# SCH-10-Power_Connectors_copy.net
KiCad netlist of a schematic drawn in Altium Designer
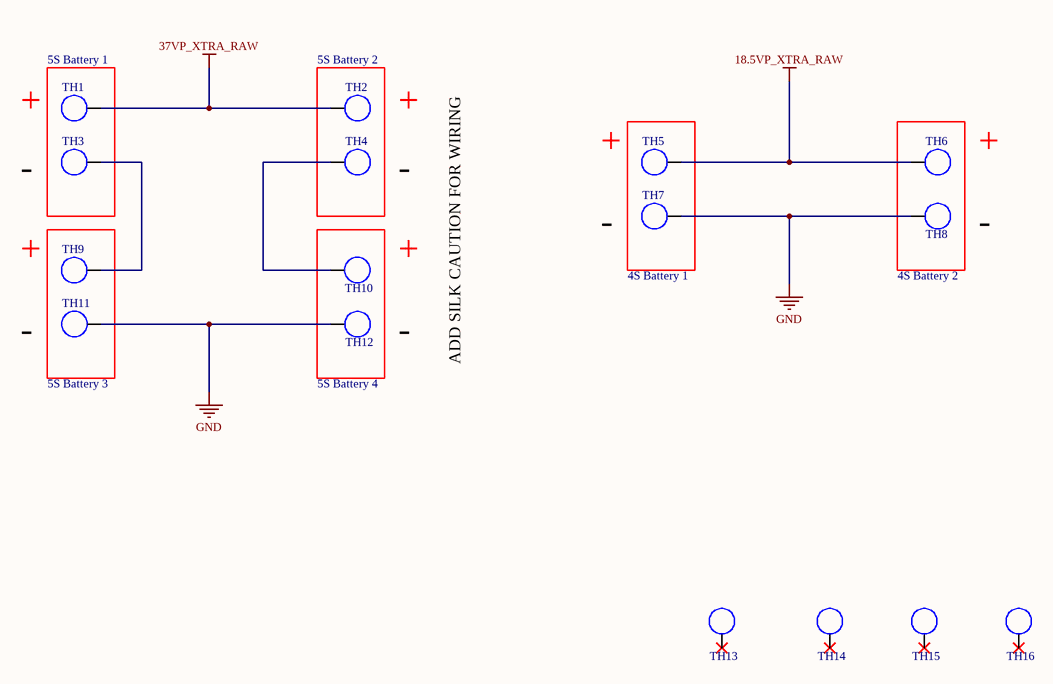
[diagram p0: SCH-10-Power Connectors_copy.SchDoc]

(export (version "E")
  (design (tool "Eeschema 10.0.6"))
  (components
    (comp (ref "TH1")
      (value "12AWG_TH")
      (footprint "m3screw")
      (libsource (lib "RSX_Mechanicals") (part "12AWG_TH"))
    )
    (comp (ref "TH2")
      (value "12AWG_TH")
      (footprint "m3screw")
      (libsource (lib "RSX_Mechanicals") (part "12AWG_TH"))
    )
    (comp (ref "TH3")
      (value "12AWG_TH")
      (footprint "m3screw")
      (libsource (lib "RSX_Mechanicals") (part "12AWG_TH"))
    )
    (comp (ref "TH4")
      (value "12AWG_TH")
      (footprint "m3screw")
      (libsource (lib "RSX_Mechanicals") (part "12AWG_TH"))
    )
    (comp (ref "TH5")
      (value "10AWG_TH")
      (footprint "m3screw")
      (libsource (lib "RSX_Mechanicals") (part "10AWG_TH"))
    )
    (comp (ref "TH6")
      (value "10AWG_TH")
      (footprint "m3screw")
      (libsource (lib "RSX_Mechanicals") (part "10AWG_TH"))
    )
    (comp (ref "TH7")
      (value "10AWG_TH")
      (footprint "m3screw")
      (libsource (lib "RSX_Mechanicals") (part "10AWG_TH"))
    )
    (comp (ref "TH8")
      (value "10AWG_TH")
      (footprint "m3screw")
      (libsource (lib "RSX_Mechanicals") (part "10AWG_TH"))
    )
    (comp (ref "TH9")
      (value "10AWG_TH")
      (footprint "m3screw")
      (libsource (lib "RSX_Mechanicals") (part "10AWG_TH"))
    )
    (comp (ref "TH10")
      (value "10AWG_TH")
      (footprint "m3screw")
      (libsource (lib "RSX_Mechanicals") (part "10AWG_TH"))
    )
    (comp (ref "TH11")
      (value "10AWG_TH")
      (footprint "m3screw")
      (libsource (lib "RSX_Mechanicals") (part "10AWG_TH"))
    )
    (comp (ref "TH12")
      (value "10AWG_TH")
      (footprint "m3screw")
      (libsource (lib "RSX_Mechanicals") (part "10AWG_TH"))
    )
    (comp (ref "TH13")
      (value "10AWG_TH")
      (footprint "m3screw")
      (libsource (lib "RSX_Mechanicals") (part "10AWG_TH"))
    )
    (comp (ref "TH14")
      (value "10AWG_TH")
      (footprint "m3screw")
      (libsource (lib "RSX_Mechanicals") (part "10AWG_TH"))
    )
    (comp (ref "TH15")
      (value "10AWG_TH")
      (footprint "m3screw")
      (libsource (lib "RSX_Mechanicals") (part "10AWG_TH"))
    )
    (comp (ref "TH16")
      (value "10AWG_TH")
      (footprint "m3screw")
      (libsource (lib "RSX_Mechanicals") (part "10AWG_TH"))
    )
  )
  (nets
    (net (code "1") (name "18.5VP_XTRA_RAW") (class "Default")
      (node (ref "TH5") (pin "1") (pinfunction "1_1") (pintype "passive"))
      (node (ref "TH6") (pin "1") (pinfunction "1_1") (pintype "passive"))
    )
    (net (code "2") (name "37VP_XTRA_RAW") (class "Default")
      (node (ref "TH1") (pin "1") (pinfunction "1_1") (pintype "passive"))
      (node (ref "TH2") (pin "1") (pinfunction "1_1") (pintype "passive"))
    )
    (net (code "3") (name "GND") (class "Default")
      (node (ref "TH11") (pin "1") (pinfunction "1_1") (pintype "passive"))
      (node (ref "TH12") (pin "1") (pinfunction "1_1") (pintype "passive"))
      (node (ref "TH7") (pin "1") (pinfunction "1_1") (pintype "passive"))
      (node (ref "TH8") (pin "1") (pinfunction "1_1") (pintype "passive"))
    )
    (net (code "4") (name "Net-(TH3-Pad1)") (class "Default")
      (node (ref "TH3") (pin "1") (pinfunction "1_1") (pintype "passive"))
      (node (ref "TH9") (pin "1") (pinfunction "1_1") (pintype "passive"))
    )
    (net (code "5") (name "Net-(TH10-Pad1)") (class "Default")
      (node (ref "TH10") (pin "1") (pinfunction "1_1") (pintype "passive"))
      (node (ref "TH4") (pin "1") (pinfunction "1_1") (pintype "passive"))
    )
    (net (code "6") (name "unconnected-(TH13-Pad1)") (class "Default")
      (node (ref "TH13") (pin "1") (pinfunction "1_1") (pintype "passive+no_connect"))
    )
    (net (code "7") (name "unconnected-(TH14-Pad1)") (class "Default")
      (node (ref "TH14") (pin "1") (pinfunction "1_1") (pintype "passive+no_connect"))
    )
    (net (code "8") (name "unconnected-(TH15-Pad1)") (class "Default")
      (node (ref "TH15") (pin "1") (pinfunction "1_1") (pintype "passive+no_connect"))
    )
    (net (code "9") (name "unconnected-(TH16-Pad1)") (class "Default")
      (node (ref "TH16") (pin "1") (pinfunction "1_1") (pintype "passive+no_connect"))
    )
  )
)
